# M-LVDS_PHY.net
KiCad netlist of a schematic drawn in Altium Designer
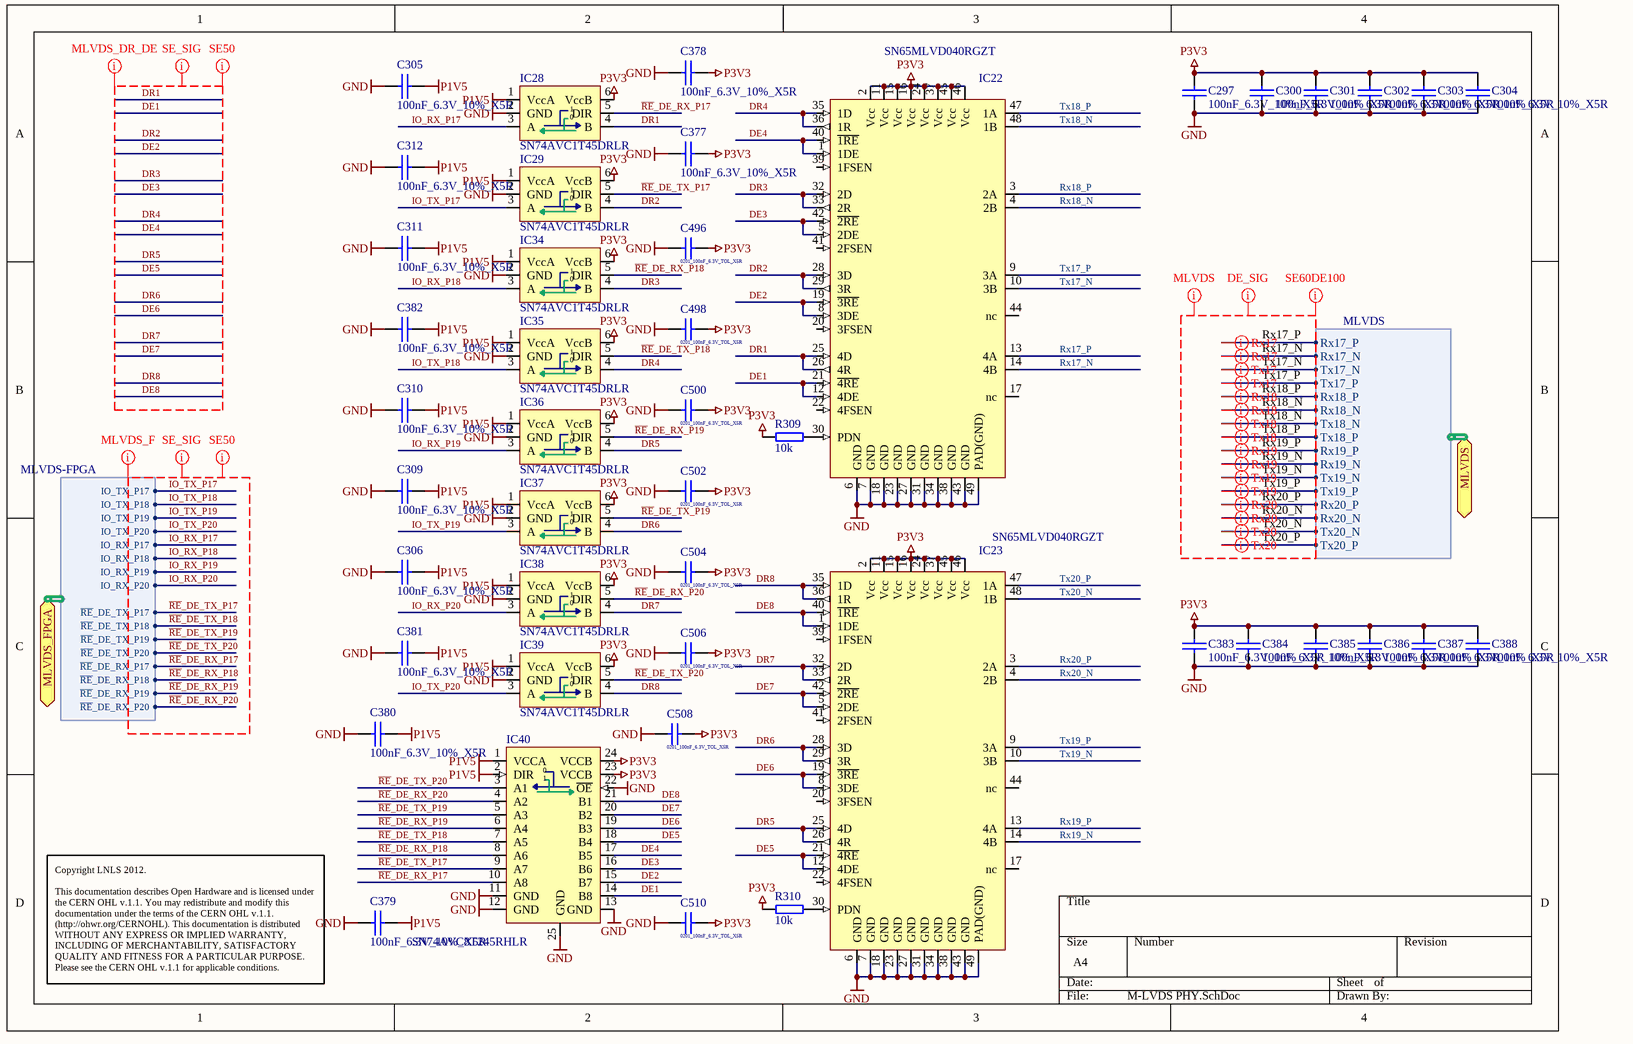
[diagram p0: M-LVDS PHY.SchDoc]

(export (version "E")
  (design (tool "Eeschema 10.0.6"))
  (components
    (comp (ref "C297")
      (value "100nF_6.3V_10%_X5R")
      (footprint "0201C")
      (description "Capacitor SMD")
      (libsource (lib "LIBRARY_SCH") (part "CAP_SMD_0201"))
    )
    (comp (ref "C300")
      (value "100nF_6.3V_10%_X5R")
      (footprint "0201C")
      (description "Capacitor SMD")
      (libsource (lib "LIBRARY_SCH") (part "CAP_SMD_0201"))
    )
    (comp (ref "C301")
      (value "100nF_6.3V_10%_X5R")
      (footprint "0201C")
      (description "Capacitor SMD")
      (libsource (lib "LIBRARY_SCH") (part "CAP_SMD_0201"))
    )
    (comp (ref "C302")
      (value "100nF_6.3V_10%_X5R")
      (footprint "0201C")
      (description "Capacitor SMD")
      (libsource (lib "LIBRARY_SCH") (part "CAP_SMD_0201"))
    )
    (comp (ref "C303")
      (value "100nF_6.3V_10%_X5R")
      (footprint "0201C")
      (description "Capacitor SMD")
      (libsource (lib "LIBRARY_SCH") (part "CAP_SMD_0201"))
    )
    (comp (ref "C304")
      (value "100nF_6.3V_10%_X5R")
      (footprint "0201C")
      (description "Capacitor SMD")
      (libsource (lib "LIBRARY_SCH") (part "CAP_SMD_0201"))
    )
    (comp (ref "C305")
      (value "100nF_6.3V_10%_X5R")
      (footprint "0201C")
      (description "Capacitor SMD")
      (libsource (lib "LIBRARY_SCH") (part "CAP_SMD_0201"))
    )
    (comp (ref "C306")
      (value "100nF_6.3V_10%_X5R")
      (footprint "0201C")
      (description "Capacitor SMD")
      (libsource (lib "LIBRARY_SCH") (part "CAP_SMD_0201"))
    )
    (comp (ref "C309")
      (value "100nF_6.3V_10%_X5R")
      (footprint "0201C")
      (description "Capacitor SMD")
      (libsource (lib "LIBRARY_SCH") (part "CAP_SMD_0201"))
    )
    (comp (ref "C310")
      (value "100nF_6.3V_10%_X5R")
      (footprint "0201C")
      (description "Capacitor SMD")
      (libsource (lib "LIBRARY_SCH") (part "CAP_SMD_0201"))
    )
    (comp (ref "C311")
      (value "100nF_6.3V_10%_X5R")
      (footprint "0201C")
      (description "Capacitor SMD")
      (libsource (lib "LIBRARY_SCH") (part "CAP_SMD_0201"))
    )
    (comp (ref "C312")
      (value "100nF_6.3V_10%_X5R")
      (footprint "0201C")
      (description "Capacitor SMD")
      (libsource (lib "LIBRARY_SCH") (part "CAP_SMD_0201"))
    )
    (comp (ref "C377")
      (value "100nF_6.3V_10%_X5R")
      (footprint "0201C")
      (description "Capacitor SMD")
      (libsource (lib "LIBRARY_SCH") (part "CAP_SMD_0201"))
    )
    (comp (ref "C378")
      (value "100nF_6.3V_10%_X5R")
      (footprint "0201C")
      (description "Capacitor SMD")
      (libsource (lib "LIBRARY_SCH") (part "CAP_SMD_0201"))
    )
    (comp (ref "C379")
      (value "100nF_6.3V_10%_X5R")
      (footprint "0201C")
      (description "Capacitor SMD")
      (libsource (lib "LIBRARY_SCH") (part "CAP_SMD_0201"))
    )
    (comp (ref "C380")
      (value "100nF_6.3V_10%_X5R")
      (footprint "0201C")
      (description "Capacitor SMD")
      (libsource (lib "LIBRARY_SCH") (part "CAP_SMD_0201"))
    )
    (comp (ref "C381")
      (value "100nF_6.3V_10%_X5R")
      (footprint "0201C")
      (description "Capacitor SMD")
      (libsource (lib "LIBRARY_SCH") (part "CAP_SMD_0201"))
    )
    (comp (ref "C382")
      (value "100nF_6.3V_10%_X5R")
      (footprint "0201C")
      (description "Capacitor SMD")
      (libsource (lib "LIBRARY_SCH") (part "CAP_SMD_0201"))
    )
    (comp (ref "C383")
      (value "100nF_6.3V_10%_X5R")
      (footprint "0201C")
      (description "Capacitor SMD")
      (libsource (lib "LIBRARY_SCH") (part "CAP_SMD_0201"))
    )
    (comp (ref "C384")
      (value "100nF_6.3V_10%_X5R")
      (footprint "0201C")
      (description "Capacitor SMD")
      (libsource (lib "LIBRARY_SCH") (part "CAP_SMD_0201"))
    )
    (comp (ref "C385")
      (value "100nF_6.3V_10%_X5R")
      (footprint "0201C")
      (description "Capacitor SMD")
      (libsource (lib "LIBRARY_SCH") (part "CAP_SMD_0201"))
    )
    (comp (ref "C386")
      (value "100nF_6.3V_10%_X5R")
      (footprint "0201C")
      (description "Capacitor SMD")
      (libsource (lib "LIBRARY_SCH") (part "CAP_SMD_0201"))
    )
    (comp (ref "C387")
      (value "100nF_6.3V_10%_X5R")
      (footprint "0201C")
      (description "Capacitor SMD")
      (libsource (lib "LIBRARY_SCH") (part "CAP_SMD_0201"))
    )
    (comp (ref "C388")
      (value "100nF_6.3V_10%_X5R")
      (footprint "0201C")
      (description "Capacitor SMD")
      (libsource (lib "LIBRARY_SCH") (part "CAP_SMD_0201"))
    )
    (comp (ref "C496")
      (value "0201_100nF_6.3V_TOL_X5R")
      (footprint "CAPC0603X33N")
      (fields (field (name "PART NUMBER") "Ceramic_0201"))
      (libsource (lib "Capacitors") (part "Capacitor"))
    )
    (comp (ref "C498")
      (value "0201_100nF_6.3V_TOL_X5R")
      (footprint "CAPC0603X33N")
      (fields (field (name "PART NUMBER") "Ceramic_0201"))
      (libsource (lib "Capacitors") (part "Capacitor"))
    )
    (comp (ref "C500")
      (value "0201_100nF_6.3V_TOL_X5R")
      (footprint "CAPC0603X33N")
      (fields (field (name "PART NUMBER") "Ceramic_0201"))
      (libsource (lib "Capacitors") (part "Capacitor"))
    )
    (comp (ref "C502")
      (value "0201_100nF_6.3V_TOL_X5R")
      (footprint "CAPC0603X33N")
      (fields (field (name "PART NUMBER") "Ceramic_0201"))
      (libsource (lib "Capacitors") (part "Capacitor"))
    )
    (comp (ref "C504")
      (value "0201_100nF_6.3V_TOL_X5R")
      (footprint "CAPC0603X33N")
      (fields (field (name "PART NUMBER") "Ceramic_0201"))
      (libsource (lib "Capacitors") (part "Capacitor"))
    )
    (comp (ref "C506")
      (value "0201_100nF_6.3V_TOL_X5R")
      (footprint "CAPC0603X33N")
      (fields (field (name "PART NUMBER") "Ceramic_0201"))
      (libsource (lib "Capacitors") (part "Capacitor"))
    )
    (comp (ref "C508")
      (value "0201_100nF_6.3V_TOL_X5R")
      (footprint "CAPC0603X33N")
      (fields (field (name "PART NUMBER") "Ceramic_0201"))
      (libsource (lib "Capacitors") (part "Capacitor"))
    )
    (comp (ref "C510")
      (value "0201_100nF_6.3V_TOL_X5R")
      (footprint "CAPC0603X33N")
      (fields (field (name "PART NUMBER") "Ceramic_0201"))
      (libsource (lib "Capacitors") (part "Capacitor"))
    )
    (comp (ref "IC22")
      (value "SN65MLVD040RGZT")
      (footprint "QFN48L")
      (libsource (lib "LIBRARY_SCH") (part "IFC_SN65MLVD040"))
    )
    (comp (ref "IC23")
      (value "SN65MLVD040RGZT")
      (footprint "QFN48L")
      (libsource (lib "LIBRARY_SCH") (part "IFC_SN65MLVD040"))
    )
    (comp (ref "IC28")
      (value "SN74AVC1T45DRLR")
      (footprint "SOT-553")
      (description "1-bit Transceiver Dual Supply (1.4...3.6V)")
      (libsource (lib "LIBRARY_SCH") (part "74AVC1T45"))
    )
    (comp (ref "IC29")
      (value "SN74AVC1T45DRLR")
      (footprint "SOT-553")
      (description "1-bit Transceiver Dual Supply (1.4...3.6V)")
      (libsource (lib "LIBRARY_SCH") (part "74AVC1T45"))
    )
    (comp (ref "IC34")
      (value "SN74AVC1T45DRLR")
      (footprint "SOT-553")
      (description "1-bit Transceiver Dual Supply (1.4...3.6V)")
      (libsource (lib "LIBRARY_SCH") (part "74AVC1T45"))
    )
    (comp (ref "IC35")
      (value "SN74AVC1T45DRLR")
      (footprint "SOT-553")
      (description "1-bit Transceiver Dual Supply (1.4...3.6V)")
      (libsource (lib "LIBRARY_SCH") (part "74AVC1T45"))
    )
    (comp (ref "IC36")
      (value "SN74AVC1T45DRLR")
      (footprint "SOT-553")
      (description "1-bit Transceiver Dual Supply (1.4...3.6V)")
      (libsource (lib "LIBRARY_SCH") (part "74AVC1T45"))
    )
    (comp (ref "IC37")
      (value "SN74AVC1T45DRLR")
      (footprint "SOT-553")
      (description "1-bit Transceiver Dual Supply (1.4...3.6V)")
      (libsource (lib "LIBRARY_SCH") (part "74AVC1T45"))
    )
    (comp (ref "IC38")
      (value "SN74AVC1T45DRLR")
      (footprint "SOT-553")
      (description "1-bit Transceiver Dual Supply (1.4...3.6V)")
      (libsource (lib "LIBRARY_SCH") (part "74AVC1T45"))
    )
    (comp (ref "IC39")
      (value "SN74AVC1T45DRLR")
      (footprint "SOT-553")
      (description "1-bit Transceiver Dual Supply (1.4...3.6V)")
      (libsource (lib "LIBRARY_SCH") (part "74AVC1T45"))
    )
    (comp (ref "IC40")
      (value "SN74AVC8T245RHLR")
      (footprint "QFN50P350X550X100-24N")
      (description "8 channel bidir translator buffer (1.4..3.6V)")
      (libsource (lib "LIBRARY_SCH") (part "74AVC8T245_QFN"))
    )
    (comp (ref "R309")
      (value "10k")
      (footprint "0402R")
      (description "SMD Resistor")
      (libsource (lib "LIBRARY_SCH") (part "RES_0402"))
    )
    (comp (ref "R310")
      (value "10k")
      (footprint "0402R")
      (description "SMD Resistor")
      (libsource (lib "LIBRARY_SCH") (part "RES_0402"))
    )
  )
  (nets
    (net (code "3") (name "/DE1") (class "Default")
      (node (ref "IC22") (pin "12") (pinfunction "4DE_12") (pintype "input"))
      (node (ref "IC22") (pin "21") (pinfunction "~{4RE}_21") (pintype "input"))
      (node (ref "IC40") (pin "14") (pinfunction "B8_14") (pintype "bidirectional"))
    )
    (net (code "4") (name "/DE2") (class "Default")
      (node (ref "IC22") (pin "19") (pinfunction "~{3RE}_19") (pintype "input"))
      (node (ref "IC22") (pin "8") (pinfunction "3DE_8") (pintype "input"))
      (node (ref "IC40") (pin "15") (pinfunction "B7_15") (pintype "bidirectional"))
    )
    (net (code "5") (name "/DE3") (class "Default")
      (node (ref "IC22") (pin "42") (pinfunction "~{2RE}_42") (pintype "input"))
      (node (ref "IC22") (pin "5") (pinfunction "2DE_5") (pintype "input"))
      (node (ref "IC40") (pin "16") (pinfunction "B6_16") (pintype "bidirectional"))
    )
    (net (code "6") (name "/DE4") (class "Default")
      (node (ref "IC22") (pin "1") (pinfunction "1DE_1") (pintype "input"))
      (node (ref "IC22") (pin "40") (pinfunction "~{1RE}_40") (pintype "input"))
      (node (ref "IC40") (pin "17") (pinfunction "B5_17") (pintype "bidirectional"))
    )
    (net (code "7") (name "/DE5") (class "Default")
      (node (ref "IC23") (pin "12") (pinfunction "4DE_12") (pintype "input"))
      (node (ref "IC23") (pin "21") (pinfunction "~{4RE}_21") (pintype "input"))
      (node (ref "IC40") (pin "18") (pinfunction "B4_18") (pintype "bidirectional"))
    )
    (net (code "8") (name "/DE6") (class "Default")
      (node (ref "IC23") (pin "19") (pinfunction "~{3RE}_19") (pintype "input"))
      (node (ref "IC23") (pin "8") (pinfunction "3DE_8") (pintype "input"))
      (node (ref "IC40") (pin "19") (pinfunction "B3_19") (pintype "bidirectional"))
    )
    (net (code "9") (name "/DE7") (class "Default")
      (node (ref "IC23") (pin "42") (pinfunction "~{2RE}_42") (pintype "input"))
      (node (ref "IC23") (pin "5") (pinfunction "2DE_5") (pintype "input"))
      (node (ref "IC40") (pin "20") (pinfunction "B2_20") (pintype "bidirectional"))
    )
    (net (code "10") (name "/DE8") (class "Default")
      (node (ref "IC23") (pin "1") (pinfunction "1DE_1") (pintype "input"))
      (node (ref "IC23") (pin "40") (pinfunction "~{1RE}_40") (pintype "input"))
      (node (ref "IC40") (pin "21") (pinfunction "B1_21") (pintype "bidirectional"))
    )
    (net (code "11") (name "/DR1") (class "Default")
      (node (ref "IC22") (pin "25") (pinfunction "4D_25") (pintype "input"))
      (node (ref "IC22") (pin "26") (pinfunction "4R_26") (pintype "output"))
      (node (ref "IC28") (pin "4") (pinfunction "B_4") (pintype "passive"))
    )
    (net (code "12") (name "/DR2") (class "Default")
      (node (ref "IC22") (pin "28") (pinfunction "3D_28") (pintype "input"))
      (node (ref "IC22") (pin "29") (pinfunction "3R_29") (pintype "output"))
      (node (ref "IC29") (pin "4") (pinfunction "B_4") (pintype "passive"))
    )
    (net (code "13") (name "/DR3") (class "Default")
      (node (ref "IC22") (pin "32") (pinfunction "2D_32") (pintype "input"))
      (node (ref "IC22") (pin "33") (pinfunction "2R_33") (pintype "output"))
      (node (ref "IC34") (pin "4") (pinfunction "B_4") (pintype "passive"))
    )
    (net (code "14") (name "/DR4") (class "Default")
      (node (ref "IC22") (pin "35") (pinfunction "1D_35") (pintype "input"))
      (node (ref "IC22") (pin "36") (pinfunction "1R_36") (pintype "output"))
      (node (ref "IC35") (pin "4") (pinfunction "B_4") (pintype "passive"))
    )
    (net (code "15") (name "/DR5") (class "Default")
      (node (ref "IC23") (pin "25") (pinfunction "4D_25") (pintype "input"))
      (node (ref "IC23") (pin "26") (pinfunction "4R_26") (pintype "output"))
      (node (ref "IC36") (pin "4") (pinfunction "B_4") (pintype "passive"))
    )
    (net (code "16") (name "/DR6") (class "Default")
      (node (ref "IC23") (pin "28") (pinfunction "3D_28") (pintype "input"))
      (node (ref "IC23") (pin "29") (pinfunction "3R_29") (pintype "output"))
      (node (ref "IC37") (pin "4") (pinfunction "B_4") (pintype "passive"))
    )
    (net (code "17") (name "/DR7") (class "Default")
      (node (ref "IC23") (pin "32") (pinfunction "2D_32") (pintype "input"))
      (node (ref "IC23") (pin "33") (pinfunction "2R_33") (pintype "output"))
      (node (ref "IC38") (pin "4") (pinfunction "B_4") (pintype "passive"))
    )
    (net (code "18") (name "/DR8") (class "Default")
      (node (ref "IC23") (pin "35") (pinfunction "1D_35") (pintype "input"))
      (node (ref "IC23") (pin "36") (pinfunction "1R_36") (pintype "output"))
      (node (ref "IC39") (pin "4") (pinfunction "B_4") (pintype "passive"))
    )
    (net (code "19") (name "/IO_RX_P17") (class "Default")
      (node (ref "IC28") (pin "3") (pinfunction "A_3") (pintype "passive"))
    )
    (net (code "20") (name "/IO_RX_P18") (class "Default")
      (node (ref "IC34") (pin "3") (pinfunction "A_3") (pintype "passive"))
    )
    (net (code "21") (name "/IO_RX_P19") (class "Default")
      (node (ref "IC36") (pin "3") (pinfunction "A_3") (pintype "passive"))
    )
    (net (code "22") (name "/IO_RX_P20") (class "Default")
      (node (ref "IC38") (pin "3") (pinfunction "A_3") (pintype "passive"))
    )
    (net (code "23") (name "/IO_TX_P17") (class "Default")
      (node (ref "IC29") (pin "3") (pinfunction "A_3") (pintype "passive"))
    )
    (net (code "24") (name "/IO_TX_P18") (class "Default")
      (node (ref "IC35") (pin "3") (pinfunction "A_3") (pintype "passive"))
    )
    (net (code "25") (name "/IO_TX_P19") (class "Default")
      (node (ref "IC37") (pin "3") (pinfunction "A_3") (pintype "passive"))
    )
    (net (code "26") (name "/IO_TX_P20") (class "Default")
      (node (ref "IC39") (pin "3") (pinfunction "A_3") (pintype "passive"))
    )
    (net (code "27") (name "/Rx17_N") (class "Default")
      (node (ref "IC22") (pin "14") (pinfunction "4B_14") (pintype "bidirectional"))
    )
    (net (code "28") (name "/Rx17_P") (class "Default")
      (node (ref "IC22") (pin "13") (pinfunction "4A_13") (pintype "bidirectional"))
    )
    (net (code "29") (name "/Rx18_N") (class "Default")
      (node (ref "IC22") (pin "4") (pinfunction "2B_4") (pintype "bidirectional"))
    )
    (net (code "30") (name "/Rx18_P") (class "Default")
      (node (ref "IC22") (pin "3") (pinfunction "2A_3") (pintype "bidirectional"))
    )
    (net (code "31") (name "/Rx19_N") (class "Default")
      (node (ref "IC23") (pin "14") (pinfunction "4B_14") (pintype "bidirectional"))
    )
    (net (code "32") (name "/Rx19_P") (class "Default")
      (node (ref "IC23") (pin "13") (pinfunction "4A_13") (pintype "bidirectional"))
    )
    (net (code "33") (name "/Rx20_N") (class "Default")
      (node (ref "IC23") (pin "4") (pinfunction "2B_4") (pintype "bidirectional"))
    )
    (net (code "34") (name "/Rx20_P") (class "Default")
      (node (ref "IC23") (pin "3") (pinfunction "2A_3") (pintype "bidirectional"))
    )
    (net (code "35") (name "/Tx17_N") (class "Default")
      (node (ref "IC22") (pin "10") (pinfunction "3B_10") (pintype "bidirectional"))
    )
    (net (code "36") (name "/Tx17_P") (class "Default")
      (node (ref "IC22") (pin "9") (pinfunction "3A_9") (pintype "bidirectional"))
    )
    (net (code "37") (name "/Tx18_N") (class "Default")
      (node (ref "IC22") (pin "48") (pinfunction "1B_48") (pintype "bidirectional"))
    )
    (net (code "38") (name "/Tx18_P") (class "Default")
      (node (ref "IC22") (pin "47") (pinfunction "1A_47") (pintype "bidirectional"))
    )
    (net (code "39") (name "/Tx19_N") (class "Default")
      (node (ref "IC23") (pin "10") (pinfunction "3B_10") (pintype "bidirectional"))
    )
    (net (code "40") (name "/Tx19_P") (class "Default")
      (node (ref "IC23") (pin "9") (pinfunction "3A_9") (pintype "bidirectional"))
    )
    (net (code "41") (name "/Tx20_N") (class "Default")
      (node (ref "IC23") (pin "48") (pinfunction "1B_48") (pintype "bidirectional"))
    )
    (net (code "42") (name "/Tx20_P") (class "Default")
      (node (ref "IC23") (pin "47") (pinfunction "1A_47") (pintype "bidirectional"))
    )
    (net (code "45") (name "/~{RE}_DE_RX_P17") (class "Default")
      (node (ref "IC28") (pin "5") (pinfunction "DIR_5") (pintype "passive"))
      (node (ref "IC40") (pin "10") (pinfunction "A8_10") (pintype "bidirectional"))
    )
    (net (code "46") (name "/~{RE}_DE_RX_P18") (class "Default")
      (node (ref "IC34") (pin "5") (pinfunction "DIR_5") (pintype "passive"))
      (node (ref "IC40") (pin "8") (pinfunction "A6_8") (pintype "bidirectional"))
    )
    (net (code "47") (name "/~{RE}_DE_RX_P19") (class "Default")
      (node (ref "IC36") (pin "5") (pinfunction "DIR_5") (pintype "passive"))
      (node (ref "IC40") (pin "6") (pinfunction "A4_6") (pintype "bidirectional"))
    )
    (net (code "48") (name "/~{RE}_DE_RX_P20") (class "Default")
      (node (ref "IC38") (pin "5") (pinfunction "DIR_5") (pintype "passive"))
      (node (ref "IC40") (pin "4") (pinfunction "A2_4") (pintype "bidirectional"))
    )
    (net (code "49") (name "/~{RE}_DE_TX_P17") (class "Default")
      (node (ref "IC29") (pin "5") (pinfunction "DIR_5") (pintype "passive"))
      (node (ref "IC40") (pin "9") (pinfunction "A7_9") (pintype "bidirectional"))
    )
    (net (code "50") (name "/~{RE}_DE_TX_P18") (class "Default")
      (node (ref "IC35") (pin "5") (pinfunction "DIR_5") (pintype "passive"))
      (node (ref "IC40") (pin "7") (pinfunction "A5_7") (pintype "bidirectional"))
    )
    (net (code "51") (name "/~{RE}_DE_TX_P19") (class "Default")
      (node (ref "IC37") (pin "5") (pinfunction "DIR_5") (pintype "passive"))
      (node (ref "IC40") (pin "5") (pinfunction "A3_5") (pintype "bidirectional"))
    )
    (net (code "52") (name "/~{RE}_DE_TX_P20") (class "Default")
      (node (ref "IC39") (pin "5") (pinfunction "DIR_5") (pintype "passive"))
      (node (ref "IC40") (pin "3") (pinfunction "A1_3") (pintype "bidirectional"))
    )
    (net (code "53") (name "GND") (class "Default")
      (node (ref "C297") (pin "2") (pinfunction "2_2") (pintype "passive"))
      (node (ref "C300") (pin "2") (pinfunction "2_2") (pintype "passive"))
      (node (ref "C301") (pin "2") (pinfunction "2_2") (pintype "passive"))
      (node (ref "C302") (pin "2") (pinfunction "2_2") (pintype "passive"))
      (node (ref "C303") (pin "2") (pinfunction "2_2") (pintype "passive"))
      (node (ref "C304") (pin "2") (pinfunction "2_2") (pintype "passive"))
      (node (ref "C305") (pin "2") (pinfunction "2_2") (pintype "passive"))
      (node (ref "C306") (pin "1") (pinfunction "1_1") (pintype "passive"))
      (node (ref "C309") (pin "1") (pinfunction "1_1") (pintype "passive"))
      (node (ref "C310") (pin "1") (pinfunction "1_1") (pintype "passive"))
      (node (ref "C311") (pin "1") (pinfunction "1_1") (pintype "passive"))
      (node (ref "C312") (pin "1") (pinfunction "1_1") (pintype "passive"))
      (node (ref "C377") (pin "1") (pinfunction "1_1") (pintype "passive"))
      (node (ref "C378") (pin "1") (pinfunction "1_1") (pintype "passive"))
      (node (ref "C379") (pin "1") (pinfunction "1_1") (pintype "passive"))
      (node (ref "C380") (pin "1") (pinfunction "1_1") (pintype "passive"))
      (node (ref "C381") (pin "1") (pinfunction "1_1") (pintype "passive"))
      (node (ref "C382") (pin "1") (pinfunction "1_1") (pintype "passive"))
      (node (ref "C383") (pin "2") (pinfunction "2_2") (pintype "passive"))
      (node (ref "C384") (pin "2") (pinfunction "2_2") (pintype "passive"))
      (node (ref "C385") (pin "2") (pinfunction "2_2") (pintype "passive"))
      (node (ref "C386") (pin "2") (pinfunction "2_2") (pintype "passive"))
      (node (ref "C387") (pin "2") (pinfunction "2_2") (pintype "passive"))
      (node (ref "C388") (pin "2") (pinfunction "2_2") (pintype "passive"))
      (node (ref "C496") (pin "2") (pinfunction "2_2") (pintype "passive"))
      (node (ref "C498") (pin "2") (pinfunction "2_2") (pintype "passive"))
      (node (ref "C500") (pin "2") (pinfunction "2_2") (pintype "passive"))
      (node (ref "C502") (pin "2") (pinfunction "2_2") (pintype "passive"))
      (node (ref "C504") (pin "2") (pinfunction "2_2") (pintype "passive"))
      (node (ref "C506") (pin "2") (pinfunction "2_2") (pintype "passive"))
      (node (ref "C508") (pin "2") (pinfunction "2_2") (pintype "passive"))
      (node (ref "C510") (pin "2") (pinfunction "2_2") (pintype "passive"))
      (node (ref "IC22") (pin "18") (pinfunction "GND_18") (pintype "power_in"))
      (node (ref "IC22") (pin "23") (pinfunction "GND_23") (pintype "power_in"))
      (node (ref "IC22") (pin "27") (pinfunction "GND_27") (pintype "power_in"))
      (node (ref "IC22") (pin "31") (pinfunction "GND_31") (pintype "power_in"))
      (node (ref "IC22") (pin "34") (pinfunction "GND_34") (pintype "power_in"))
      (node (ref "IC22") (pin "38") (pinfunction "GND_38") (pintype "power_in"))
      (node (ref "IC22") (pin "43") (pinfunction "GND_43") (pintype "power_in"))
      (node (ref "IC22") (pin "49") (pinfunction "PAD(GND)_49") (pintype "power_in"))
      (node (ref "IC22") (pin "6") (pinfunction "GND_6") (pintype "power_in"))
      (node (ref "IC22") (pin "7") (pinfunction "GND_7") (pintype "power_in"))
      (node (ref "IC23") (pin "18") (pinfunction "GND_18") (pintype "power_in"))
      (node (ref "IC23") (pin "23") (pinfunction "GND_23") (pintype "power_in"))
      (node (ref "IC23") (pin "27") (pinfunction "GND_27") (pintype "power_in"))
      (node (ref "IC23") (pin "31") (pinfunction "GND_31") (pintype "power_in"))
      (node (ref "IC23") (pin "34") (pinfunction "GND_34") (pintype "power_in"))
      (node (ref "IC23") (pin "38") (pinfunction "GND_38") (pintype "power_in"))
      (node (ref "IC23") (pin "43") (pinfunction "GND_43") (pintype "power_in"))
      (node (ref "IC23") (pin "49") (pinfunction "PAD(GND)_49") (pintype "power_in"))
      (node (ref "IC23") (pin "6") (pinfunction "GND_6") (pintype "power_in"))
      (node (ref "IC23") (pin "7") (pinfunction "GND_7") (pintype "power_in"))
      (node (ref "IC28") (pin "2") (pinfunction "GND_2") (pintype "passive"))
      (node (ref "IC29") (pin "2") (pinfunction "GND_2") (pintype "passive"))
      (node (ref "IC34") (pin "2") (pinfunction "GND_2") (pintype "passive"))
      (node (ref "IC35") (pin "2") (pinfunction "GND_2") (pintype "passive"))
      (node (ref "IC36") (pin "2") (pinfunction "GND_2") (pintype "passive"))
      (node (ref "IC37") (pin "2") (pinfunction "GND_2") (pintype "passive"))
      (node (ref "IC38") (pin "2") (pinfunction "GND_2") (pintype "passive"))
      (node (ref "IC39") (pin "2") (pinfunction "GND_2") (pintype "passive"))
      (node (ref "IC40") (pin "11") (pinfunction "GND_11") (pintype "power_in"))
      (node (ref "IC40") (pin "12") (pinfunction "GND_12") (pintype "power_in"))
      (node (ref "IC40") (pin "13") (pinfunction "GND_13") (pintype "power_in"))
      (node (ref "IC40") (pin "22") (pinfunction "~{OE}_22") (pintype "input"))
      (node (ref "IC40") (pin "25") (pinfunction "GND_25") (pintype "power_in"))
    )
    (net (code "54") (name "Net-(IC22-PDN)") (class "Default")
      (node (ref "IC22") (pin "30") (pinfunction "PDN_30") (pintype "input"))
      (node (ref "R309") (pin "2") (pinfunction "2_2") (pintype "passive"))
    )
    (net (code "55") (name "Net-(IC23-PDN)") (class "Default")
      (node (ref "IC23") (pin "30") (pinfunction "PDN_30") (pintype "input"))
      (node (ref "R310") (pin "2") (pinfunction "2_2") (pintype "passive"))
    )
    (net (code "56") (name "P1V5") (class "Default")
      (node (ref "C305") (pin "1") (pinfunction "1_1") (pintype "passive"))
      (node (ref "C306") (pin "2") (pinfunction "2_2") (pintype "passive"))
      (node (ref "C309") (pin "2") (pinfunction "2_2") (pintype "passive"))
      (node (ref "C310") (pin "2") (pinfunction "2_2") (pintype "passive"))
      (node (ref "C311") (pin "2") (pinfunction "2_2") (pintype "passive"))
      (node (ref "C312") (pin "2") (pinfunction "2_2") (pintype "passive"))
      (node (ref "C379") (pin "2") (pinfunction "2_2") (pintype "passive"))
      (node (ref "C380") (pin "2") (pinfunction "2_2") (pintype "passive"))
      (node (ref "C381") (pin "2") (pinfunction "2_2") (pintype "passive"))
      (node (ref "C382") (pin "2") (pinfunction "2_2") (pintype "passive"))
      (node (ref "IC28") (pin "1") (pinfunction "VccA_1") (pintype "power_in"))
      (node (ref "IC29") (pin "1") (pinfunction "VccA_1") (pintype "power_in"))
      (node (ref "IC34") (pin "1") (pinfunction "VccA_1") (pintype "power_in"))
      (node (ref "IC35") (pin "1") (pinfunction "VccA_1") (pintype "power_in"))
      (node (ref "IC36") (pin "1") (pinfunction "VccA_1") (pintype "power_in"))
      (node (ref "IC37") (pin "1") (pinfunction "VccA_1") (pintype "power_in"))
      (node (ref "IC38") (pin "1") (pinfunction "VccA_1") (pintype "power_in"))
      (node (ref "IC39") (pin "1") (pinfunction "VccA_1") (pintype "power_in"))
      (node (ref "IC40") (pin "1") (pinfunction "VCCA_1") (pintype "power_in"))
      (node (ref "IC40") (pin "2") (pinfunction "DIR_2") (pintype "input"))
    )
    (net (code "57") (name "P3V3") (class "Default")
      (node (ref "C297") (pin "1") (pinfunction "1_1") (pintype "passive"))
      (node (ref "C300") (pin "1") (pinfunction "1_1") (pintype "passive"))
      (node (ref "C301") (pin "1") (pinfunction "1_1") (pintype "passive"))
      (node (ref "C302") (pin "1") (pinfunction "1_1") (pintype "passive"))
      (node (ref "C303") (pin "1") (pinfunction "1_1") (pintype "passive"))
      (node (ref "C304") (pin "1") (pinfunction "1_1") (pintype "passive"))
      (node (ref "C377") (pin "2") (pinfunction "2_2") (pintype "passive"))
      (node (ref "C378") (pin "2") (pinfunction "2_2") (pintype "passive"))
      (node (ref "C383") (pin "1") (pinfunction "1_1") (pintype "passive"))
      (node (ref "C384") (pin "1") (pinfunction "1_1") (pintype "passive"))
      (node (ref "C385") (pin "1") (pinfunction "1_1") (pintype "passive"))
      (node (ref "C386") (pin "1") (pinfunction "1_1") (pintype "passive"))
      (node (ref "C387") (pin "1") (pinfunction "1_1") (pintype "passive"))
      (node (ref "C388") (pin "1") (pinfunction "1_1") (pintype "passive"))
      (node (ref "C496") (pin "1") (pinfunction "1_1") (pintype "passive"))
      (node (ref "C498") (pin "1") (pinfunction "1_1") (pintype "passive"))
      (node (ref "C500") (pin "1") (pinfunction "1_1") (pintype "passive"))
      (node (ref "C502") (pin "1") (pinfunction "1_1") (pintype "passive"))
      (node (ref "C504") (pin "1") (pinfunction "1_1") (pintype "passive"))
      (node (ref "C506") (pin "1") (pinfunction "1_1") (pintype "passive"))
      (node (ref "C508") (pin "1") (pinfunction "1_1") (pintype "passive"))
      (node (ref "C510") (pin "1") (pinfunction "1_1") (pintype "passive"))
      (node (ref "IC22") (pin "11") (pinfunction "Vcc_11") (pintype "power_in"))
      (node (ref "IC22") (pin "15") (pinfunction "Vcc_15") (pintype "power_in"))
      (node (ref "IC22") (pin "16") (pinfunction "Vcc_16") (pintype "power_in"))
      (node (ref "IC22") (pin "2") (pinfunction "Vcc_2") (pintype "power_in"))
      (node (ref "IC22") (pin "24") (pinfunction "Vcc_24") (pintype "power_in"))
      (node (ref "IC22") (pin "37") (pinfunction "Vcc_37") (pintype "power_in"))
      (node (ref "IC22") (pin "45") (pinfunction "Vcc_45") (pintype "power_in"))
      (node (ref "IC22") (pin "46") (pinfunction "Vcc_46") (pintype "power_in"))
      (node (ref "IC23") (pin "11") (pinfunction "Vcc_11") (pintype "power_in"))
      (node (ref "IC23") (pin "15") (pinfunction "Vcc_15") (pintype "power_in"))
      (node (ref "IC23") (pin "16") (pinfunction "Vcc_16") (pintype "power_in"))
      (node (ref "IC23") (pin "2") (pinfunction "Vcc_2") (pintype "power_in"))
      (node (ref "IC23") (pin "24") (pinfunction "Vcc_24") (pintype "power_in"))
      (node (ref "IC23") (pin "37") (pinfunction "Vcc_37") (pintype "power_in"))
      (node (ref "IC23") (pin "45") (pinfunction "Vcc_45") (pintype "power_in"))
      (node (ref "IC23") (pin "46") (pinfunction "Vcc_46") (pintype "power_in"))
      (node (ref "IC28") (pin "6") (pinfunction "VccB_6") (pintype "passive"))
      (node (ref "IC29") (pin "6") (pinfunction "VccB_6") (pintype "passive"))
      (node (ref "IC34") (pin "6") (pinfunction "VccB_6") (pintype "passive"))
      (node (ref "IC35") (pin "6") (pinfunction "VccB_6") (pintype "passive"))
      (node (ref "IC36") (pin "6") (pinfunction "VccB_6") (pintype "passive"))
      (node (ref "IC37") (pin "6") (pinfunction "VccB_6") (pintype "passive"))
      (node (ref "IC38") (pin "6") (pinfunction "VccB_6") (pintype "passive"))
      (node (ref "IC39") (pin "6") (pinfunction "VccB_6") (pintype "passive"))
      (node (ref "IC40") (pin "23") (pinfunction "VCCB_23") (pintype "power_in"))
      (node (ref "IC40") (pin "24") (pinfunction "VCCB_24") (pintype "power_in"))
      (node (ref "R309") (pin "1") (pinfunction "1_1") (pintype "passive"))
      (node (ref "R310") (pin "1") (pinfunction "1_1") (pintype "passive"))
    )
    (net (code "58") (name "unconnected-(IC22-1FSEN-Pad39)") (class "Default")
      (node (ref "IC22") (pin "39") (pinfunction "1FSEN_39") (pintype "input"))
    )
    (net (code "59") (name "unconnected-(IC22-2FSEN-Pad41)") (class "Default")
      (node (ref "IC22") (pin "41") (pinfunction "2FSEN_41") (pintype "input"))
    )
    (net (code "60") (name "unconnected-(IC22-3FSEN-Pad20)") (class "Default")
      (node (ref "IC22") (pin "20") (pinfunction "3FSEN_20") (pintype "input"))
    )
    (net (code "61") (name "unconnected-(IC22-4FSEN-Pad22)") (class "Default")
      (node (ref "IC22") (pin "22") (pinfunction "4FSEN_22") (pintype "input"))
    )
    (net (code "62") (name "unconnected-(IC22-nc-Pad17)") (class "Default")
      (node (ref "IC22") (pin "17") (pinfunction "nc_17") (pintype "passive"))
    )
    (net (code "63") (name "unconnected-(IC22-nc-Pad44)") (class "Default")
      (node (ref "IC22") (pin "44") (pinfunction "nc_44") (pintype "power_in"))
    )
    (net (code "64") (name "unconnected-(IC23-1FSEN-Pad39)") (class "Default")
      (node (ref "IC23") (pin "39") (pinfunction "1FSEN_39") (pintype "input"))
    )
    (net (code "65") (name "unconnected-(IC23-2FSEN-Pad41)") (class "Default")
      (node (ref "IC23") (pin "41") (pinfunction "2FSEN_41") (pintype "input"))
    )
    (net (code "66") (name "unconnected-(IC23-3FSEN-Pad20)") (class "Default")
      (node (ref "IC23") (pin "20") (pinfunction "3FSEN_20") (pintype "input"))
    )
    (net (code "67") (name "unconnected-(IC23-4FSEN-Pad22)") (class "Default")
      (node (ref "IC23") (pin "22") (pinfunction "4FSEN_22") (pintype "input"))
    )
    (net (code "68") (name "unconnected-(IC23-nc-Pad17)") (class "Default")
      (node (ref "IC23") (pin "17") (pinfunction "nc_17") (pintype "passive"))
    )
    (net (code "69") (name "unconnected-(IC23-nc-Pad44)") (class "Default")
      (node (ref "IC23") (pin "44") (pinfunction "nc_44") (pintype "power_in"))
    )
  )
)
